# WaveTable.net
KiCad netlist of a schematic drawn in EAGLE
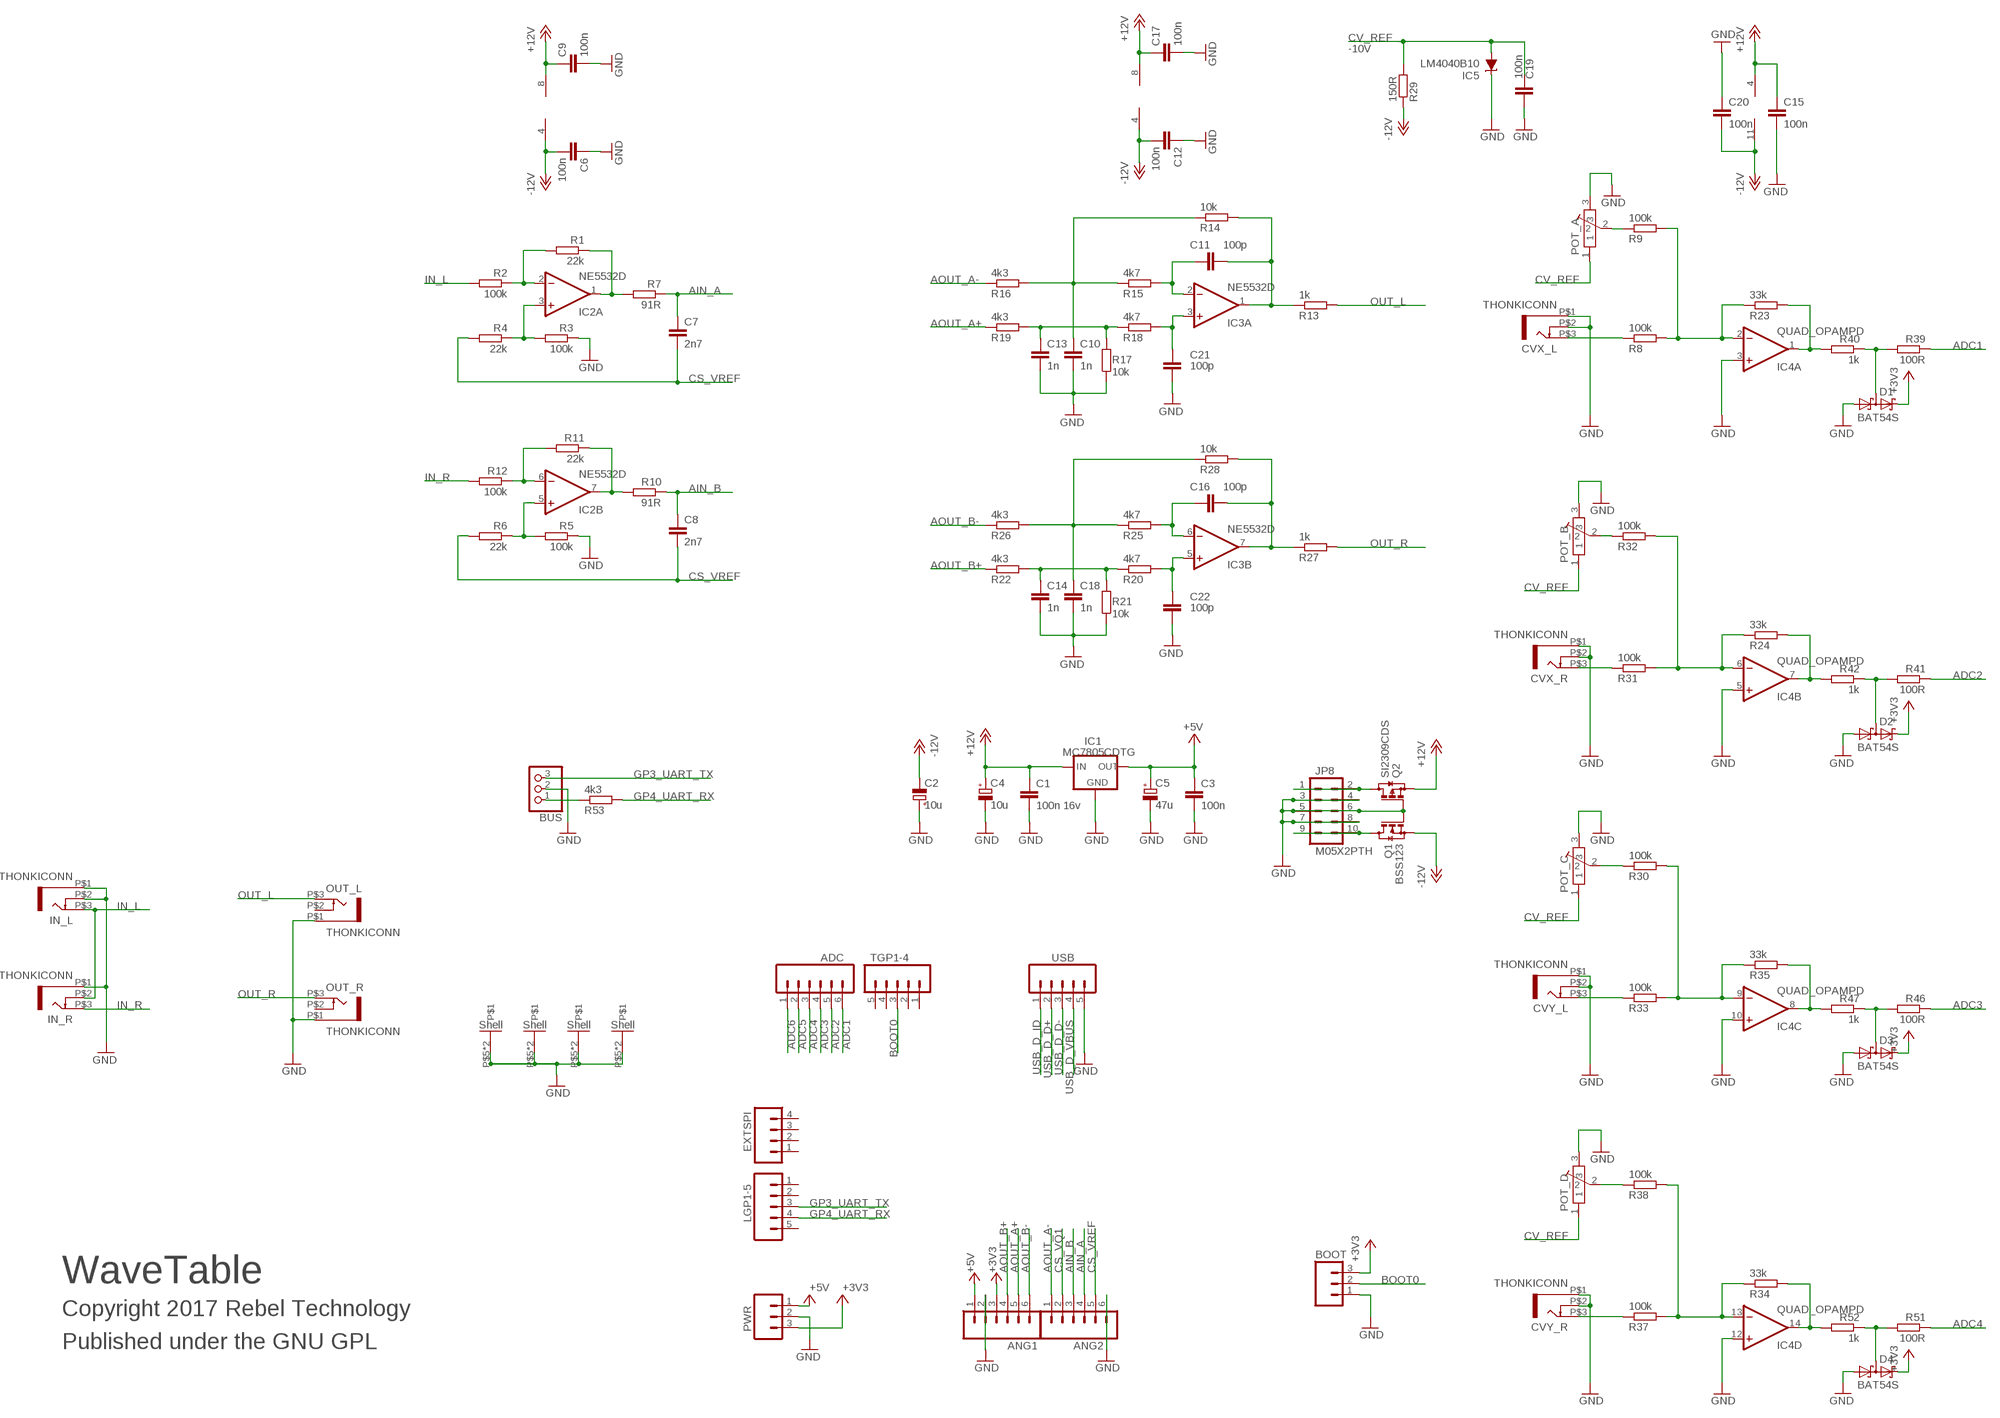
[diagram p0: schematic, sheet 1, part 1 of 2]
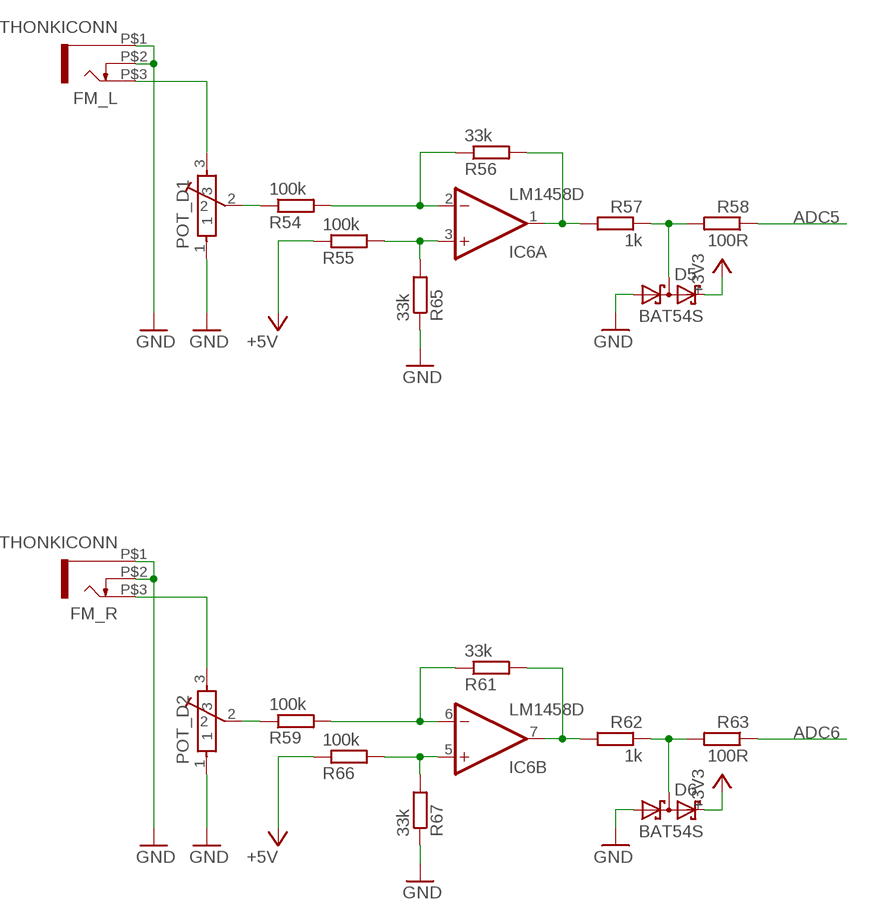
[diagram p1: schematic, sheet 1, part 2 of 2]

(export (version "E")
  (design (tool "Eeschema 10.0.6"))
  (components
    (comp (ref "ADC")
      (value "M06SIP")
      (footprint "eagle-import:1X06")
      (libsource (lib "eagle-import") (part "M06SIP"))
    )
    (comp (ref "ANG1")
      (value "M06SIP")
      (footprint "eagle-import:1X06")
      (libsource (lib "eagle-import") (part "M06SIP"))
    )
    (comp (ref "ANG2")
      (value "M06SIP")
      (footprint "eagle-import:1X06")
      (libsource (lib "eagle-import") (part "M06SIP"))
    )
    (comp (ref "BOOT")
      (value "M03PTH")
      (footprint "eagle-import:1X03")
      (libsource (lib "eagle-import") (part "M03PTH"))
    )
    (comp (ref "BUS")
      (value "CON-JST-1X03PH-TH")
      (footprint "eagle-import:JST-B3B-PH-KL")
      (libsource (lib "eagle-import") (part "CON-JST-1X03PH-TH"))
    )
    (comp (ref "C1")
      (value "100n 16v")
      (footprint "eagle-import:C0603")
      (libsource (lib "eagle-import") (part "C-EUC0603"))
    )
    (comp (ref "C2")
      (value "10u")
      (footprint "eagle-import:CPOL-5")
      (libsource (lib "eagle-import") (part "CPOL-EU153CLV-0505"))
    )
    (comp (ref "C3")
      (value "100n")
      (footprint "eagle-import:C0603")
      (libsource (lib "eagle-import") (part "C-EUC0603"))
    )
    (comp (ref "C4")
      (value "10u")
      (footprint "eagle-import:CPOL-5")
      (libsource (lib "eagle-import") (part "CPOL-EU153CLV-0505"))
    )
    (comp (ref "C5")
      (value "47u")
      (footprint "eagle-import:PANASONIC_C")
      (libsource (lib "eagle-import") (part "rcl_CPOL-EUC"))
    )
    (comp (ref "C6")
      (value "100n")
      (footprint "eagle-import:C0603")
      (libsource (lib "eagle-import") (part "resistor_C-EUC0603"))
    )
    (comp (ref "C7")
      (value "2n7")
      (footprint "eagle-import:C0603")
      (libsource (lib "eagle-import") (part "resistor_C-EUC0603"))
    )
    (comp (ref "C8")
      (value "2n7")
      (footprint "eagle-import:C0603")
      (libsource (lib "eagle-import") (part "resistor_C-EUC0603"))
    )
    (comp (ref "C9")
      (value "100n")
      (footprint "eagle-import:C0603")
      (libsource (lib "eagle-import") (part "resistor_C-EUC0603"))
    )
    (comp (ref "C10")
      (value "1n")
      (footprint "eagle-import:C0603")
      (libsource (lib "eagle-import") (part "resistor_C-EUC0603"))
    )
    (comp (ref "C11")
      (value "100p")
      (footprint "eagle-import:C0603")
      (libsource (lib "eagle-import") (part "resistor_C-EUC0603"))
    )
    (comp (ref "C12")
      (value "100n")
      (footprint "eagle-import:C0603")
      (libsource (lib "eagle-import") (part "resistor_C-EUC0603"))
    )
    (comp (ref "C13")
      (value "1n")
      (footprint "eagle-import:C0603")
      (libsource (lib "eagle-import") (part "resistor_C-EUC0603"))
    )
    (comp (ref "C14")
      (value "1n")
      (footprint "eagle-import:C0603")
      (libsource (lib "eagle-import") (part "resistor_C-EUC0603"))
    )
    (comp (ref "C15")
      (value "100n")
      (footprint "eagle-import:C0603")
      (libsource (lib "eagle-import") (part "resistor_C-EUC0603"))
    )
    (comp (ref "C16")
      (value "100p")
      (footprint "eagle-import:C0603")
      (libsource (lib "eagle-import") (part "resistor_C-EUC0603"))
    )
    (comp (ref "C17")
      (value "100n")
      (footprint "eagle-import:C0603")
      (libsource (lib "eagle-import") (part "resistor_C-EUC0603"))
    )
    (comp (ref "C18")
      (value "1n")
      (footprint "eagle-import:C0603")
      (libsource (lib "eagle-import") (part "resistor_C-EUC0603"))
    )
    (comp (ref "C19")
      (value "100n")
      (footprint "eagle-import:C0603")
      (libsource (lib "eagle-import") (part "resistor_C-EUC0603"))
    )
    (comp (ref "C20")
      (value "100n")
      (footprint "eagle-import:C0603")
      (libsource (lib "eagle-import") (part "resistor_C-EUC0603"))
    )
    (comp (ref "C21")
      (value "100p")
      (footprint "eagle-import:C0603")
      (libsource (lib "eagle-import") (part "resistor_C-EUC0603"))
    )
    (comp (ref "C22")
      (value "100p")
      (footprint "eagle-import:C0603")
      (libsource (lib "eagle-import") (part "resistor_C-EUC0603"))
    )
    (comp (ref "CVX_L")
      (value "THONKICONN")
      (footprint "eagle-import:THONKICONN")
      (libsource (lib "eagle-import") (part "THONKICONN"))
    )
    (comp (ref "CVX_R")
      (value "THONKICONN")
      (footprint "eagle-import:THONKICONN")
      (libsource (lib "eagle-import") (part "THONKICONN"))
    )
    (comp (ref "CVY_L")
      (value "THONKICONN")
      (footprint "eagle-import:THONKICONN")
      (libsource (lib "eagle-import") (part "THONKICONN"))
    )
    (comp (ref "CVY_R")
      (value "THONKICONN")
      (footprint "eagle-import:THONKICONN")
      (libsource (lib "eagle-import") (part "THONKICONN"))
    )
    (comp (ref "D1")
      (value "BAT54S")
      (footprint "eagle-import:SOT23")
      (libsource (lib "eagle-import") (part "BAT54S"))
    )
    (comp (ref "D2")
      (value "BAT54S")
      (footprint "eagle-import:SOT23")
      (libsource (lib "eagle-import") (part "BAT54S"))
    )
    (comp (ref "D3")
      (value "BAT54S")
      (footprint "eagle-import:SOT23")
      (libsource (lib "eagle-import") (part "BAT54S"))
    )
    (comp (ref "D4")
      (value "BAT54S")
      (footprint "eagle-import:SOT23")
      (libsource (lib "eagle-import") (part "BAT54S"))
    )
    (comp (ref "D5")
      (value "BAT54S")
      (footprint "eagle-import:SOT23")
      (libsource (lib "eagle-import") (part "BAT54S"))
    )
    (comp (ref "D6")
      (value "BAT54S")
      (footprint "eagle-import:SOT23")
      (libsource (lib "eagle-import") (part "BAT54S"))
    )
    (comp (ref "EXTSPI")
      (value "M04PTH")
      (footprint "eagle-import:1X04")
      (libsource (lib "eagle-import") (part "M04PTH"))
    )
    (comp (ref "FM_L")
      (value "THONKICONN")
      (footprint "eagle-import:THONKICONN")
      (libsource (lib "eagle-import") (part "THONKICONN"))
    )
    (comp (ref "FM_R")
      (value "THONKICONN")
      (footprint "eagle-import:THONKICONN")
      (libsource (lib "eagle-import") (part "THONKICONN"))
    )
    (comp (ref "IC1")
      (value "MC7805CDTG")
      (footprint "eagle-import:DPACK")
      (libsource (lib "eagle-import") (part "MC78XX"))
    )
    (comp (ref "IC2")
      (value "NE5532D")
      (footprint "eagle-import:SO08")
      (libsource (lib "eagle-import") (part "NE5532D"))
    )
    (comp (ref "IC3")
      (value "NE5532D")
      (footprint "eagle-import:SO08")
      (libsource (lib "eagle-import") (part "NE5532D"))
    )
    (comp (ref "IC4")
      (value "QUAD_OPAMPD")
      (footprint "eagle-import:SO14")
      (libsource (lib "eagle-import") (part "QUAD_OPAMPD"))
    )
    (comp (ref "IC5")
      (value "LM4040B10")
      (footprint "eagle-import:DBZ_R-PDSO-G3")
      (fields (field (name "MF") "TEXAS INSTRUMENT CONNECTORS") (field (name "MPN") "LM4041C12QDBZT"))
      (libsource (lib "eagle-import") (part "LM4041DBZC12"))
    )
    (comp (ref "IC6")
      (value "LM1458D")
      (footprint "eagle-import:SO08")
      (libsource (lib "eagle-import") (part "1458DLM"))
    )
    (comp (ref "IN_L")
      (value "THONKICONN")
      (footprint "eagle-import:THONKICONN")
      (libsource (lib "eagle-import") (part "THONKICONN"))
    )
    (comp (ref "IN_R")
      (value "THONKICONN")
      (footprint "eagle-import:THONKICONN")
      (libsource (lib "eagle-import") (part "THONKICONN"))
    )
    (comp (ref "JP8")
      (value "M05X2PTH")
      (footprint "eagle-import:AVR_ICSP")
      (libsource (lib "eagle-import") (part "M05X2PTH"))
    )
    (comp (ref "LGP1-5")
      (value "M05PTH")
      (footprint "eagle-import:1X05")
      (libsource (lib "eagle-import") (part "M05PTH"))
    )
    (comp (ref "OUT_L")
      (value "THONKICONN")
      (footprint "eagle-import:THONKICONN")
      (libsource (lib "eagle-import") (part "THONKICONN"))
    )
    (comp (ref "OUT_R")
      (value "THONKICONN")
      (footprint "eagle-import:THONKICONN")
      (libsource (lib "eagle-import") (part "THONKICONN"))
    )
    (comp (ref "POT_A")
      (value "POT-ALPS-RK09L1140")
      (footprint "eagle-import:POT-ALPS-RK09L1140")
      (libsource (lib "eagle-import") (part "POT-ALPS-RK09L1140"))
    )
    (comp (ref "POT_B")
      (value "POT-ALPS-RK09L1140")
      (footprint "eagle-import:POT-ALPS-RK09L1140")
      (libsource (lib "eagle-import") (part "POT-ALPS-RK09L1140"))
    )
    (comp (ref "POT_C")
      (value "POT-ALPS-RK09L1140")
      (footprint "eagle-import:POT-ALPS-RK09L1140")
      (libsource (lib "eagle-import") (part "POT-ALPS-RK09L1140"))
    )
    (comp (ref "POT_D")
      (value "POT-ALPS-RK09L1140")
      (footprint "eagle-import:POT-ALPS-RK09L1140")
      (libsource (lib "eagle-import") (part "POT-ALPS-RK09L1140"))
    )
    (comp (ref "POT_D1")
      (value "POT-ALPS-RK09L1140")
      (footprint "eagle-import:POT-ALPS-RK09L1140")
      (libsource (lib "eagle-import") (part "POT-ALPS-RK09L1140"))
    )
    (comp (ref "POT_D2")
      (value "POT-ALPS-RK09L1140")
      (footprint "eagle-import:POT-ALPS-RK09L1140")
      (libsource (lib "eagle-import") (part "POT-ALPS-RK09L1140"))
    )
    (comp (ref "PWR")
      (value "M03PTH")
      (footprint "eagle-import:1X03")
      (libsource (lib "eagle-import") (part "M03PTH"))
    )
    (comp (ref "Q1")
      (value "BSS123")
      (footprint "eagle-import:SOT23")
      (libsource (lib "eagle-import") (part "BSS123"))
    )
    (comp (ref "Q2")
      (value "SI2309CDS")
      (footprint "eagle-import:SOT23")
      (libsource (lib "eagle-import") (part "BSS84"))
    )
    (comp (ref "R1")
      (value "22k")
      (footprint "eagle-import:0603")
      (libsource (lib "eagle-import") (part "R-EU_0603"))
    )
    (comp (ref "R2")
      (value "100k")
      (footprint "eagle-import:0603")
      (libsource (lib "eagle-import") (part "R-EU_0603"))
    )
    (comp (ref "R3")
      (value "100k")
      (footprint "eagle-import:0603")
      (libsource (lib "eagle-import") (part "R-EU_0603"))
    )
    (comp (ref "R4")
      (value "22k")
      (footprint "eagle-import:0603")
      (libsource (lib "eagle-import") (part "R-EU_0603"))
    )
    (comp (ref "R5")
      (value "100k")
      (footprint "eagle-import:0603")
      (libsource (lib "eagle-import") (part "R-EU_0603"))
    )
    (comp (ref "R6")
      (value "22k")
      (footprint "eagle-import:0603")
      (libsource (lib "eagle-import") (part "R-EU_0603"))
    )
    (comp (ref "R7")
      (value "91R")
      (footprint "eagle-import:0603")
      (libsource (lib "eagle-import") (part "R-EU_0603"))
    )
    (comp (ref "R8")
      (value "100k")
      (footprint "eagle-import:0603")
      (libsource (lib "eagle-import") (part "R-EU_0603"))
    )
    (comp (ref "R9")
      (value "100k")
      (footprint "eagle-import:0603")
      (libsource (lib "eagle-import") (part "R-EU_0603"))
    )
    (comp (ref "R10")
      (value "91R")
      (footprint "eagle-import:0603")
      (libsource (lib "eagle-import") (part "R-EU_0603"))
    )
    (comp (ref "R11")
      (value "22k")
      (footprint "eagle-import:0603")
      (libsource (lib "eagle-import") (part "R-EU_0603"))
    )
    (comp (ref "R12")
      (value "100k")
      (footprint "eagle-import:0603")
      (libsource (lib "eagle-import") (part "R-EU_0603"))
    )
    (comp (ref "R13")
      (value "1k")
      (footprint "eagle-import:0603")
      (libsource (lib "eagle-import") (part "R-EU_0603"))
    )
    (comp (ref "R14")
      (value "10k")
      (footprint "eagle-import:0603")
      (libsource (lib "eagle-import") (part "R-EU_0603"))
    )
    (comp (ref "R15")
      (value "4k7")
      (footprint "eagle-import:0603")
      (libsource (lib "eagle-import") (part "R-EU_0603"))
    )
    (comp (ref "R16")
      (value "4k3")
      (footprint "eagle-import:0603")
      (libsource (lib "eagle-import") (part "R-EU_0603"))
    )
    (comp (ref "R17")
      (value "10k")
      (footprint "eagle-import:0603")
      (libsource (lib "eagle-import") (part "R-EU_0603"))
    )
    (comp (ref "R18")
      (value "4k7")
      (footprint "eagle-import:0603")
      (libsource (lib "eagle-import") (part "R-EU_0603"))
    )
    (comp (ref "R19")
      (value "4k3")
      (footprint "eagle-import:0603")
      (libsource (lib "eagle-import") (part "R-EU_0603"))
    )
    (comp (ref "R20")
      (value "4k7")
      (footprint "eagle-import:0603")
      (libsource (lib "eagle-import") (part "R-EU_0603"))
    )
    (comp (ref "R21")
      (value "10k")
      (footprint "eagle-import:0603")
      (libsource (lib "eagle-import") (part "R-EU_0603"))
    )
    (comp (ref "R22")
      (value "4k3")
      (footprint "eagle-import:0603")
      (libsource (lib "eagle-import") (part "R-EU_0603"))
    )
    (comp (ref "R23")
      (value "33k")
      (footprint "eagle-import:0603")
      (libsource (lib "eagle-import") (part "R-EU_0603"))
    )
    (comp (ref "R24")
      (value "33k")
      (footprint "eagle-import:0603")
      (libsource (lib "eagle-import") (part "R-EU_0603"))
    )
    (comp (ref "R25")
      (value "4k7")
      (footprint "eagle-import:0603")
      (libsource (lib "eagle-import") (part "R-EU_0603"))
    )
    (comp (ref "R26")
      (value "4k3")
      (footprint "eagle-import:0603")
      (libsource (lib "eagle-import") (part "R-EU_0603"))
    )
    (comp (ref "R27")
      (value "1k")
      (footprint "eagle-import:0603")
      (libsource (lib "eagle-import") (part "R-EU_0603"))
    )
    (comp (ref "R28")
      (value "10k")
      (footprint "eagle-import:0603")
      (libsource (lib "eagle-import") (part "R-EU_0603"))
    )
    (comp (ref "R29")
      (value "150R")
      (footprint "eagle-import:0603")
      (libsource (lib "eagle-import") (part "R-EU_0603"))
    )
    (comp (ref "R30")
      (value "100k")
      (footprint "eagle-import:0603")
      (libsource (lib "eagle-import") (part "R-EU_0603"))
    )
    (comp (ref "R31")
      (value "100k")
      (footprint "eagle-import:0603")
      (libsource (lib "eagle-import") (part "R-EU_0603"))
    )
    (comp (ref "R32")
      (value "100k")
      (footprint "eagle-import:0603")
      (libsource (lib "eagle-import") (part "R-EU_0603"))
    )
    (comp (ref "R33")
      (value "100k")
      (footprint "eagle-import:0603")
      (libsource (lib "eagle-import") (part "R-EU_0603"))
    )
    (comp (ref "R34")
      (value "33k")
      (footprint "eagle-import:0603")
      (libsource (lib "eagle-import") (part "R-EU_0603"))
    )
    (comp (ref "R35")
      (value "33k")
      (footprint "eagle-import:0603")
      (libsource (lib "eagle-import") (part "R-EU_0603"))
    )
    (comp (ref "R37")
      (value "100k")
      (footprint "eagle-import:0603")
      (libsource (lib "eagle-import") (part "R-EU_0603"))
    )
    (comp (ref "R38")
      (value "100k")
      (footprint "eagle-import:0603")
      (libsource (lib "eagle-import") (part "R-EU_0603"))
    )
    (comp (ref "R39")
      (value "100R")
      (footprint "eagle-import:0603")
      (libsource (lib "eagle-import") (part "R-EU_0603"))
    )
    (comp (ref "R40")
      (value "1k")
      (footprint "eagle-import:0603")
      (libsource (lib "eagle-import") (part "R-EU_0603"))
    )
    (comp (ref "R41")
      (value "100R")
      (footprint "eagle-import:0603")
      (libsource (lib "eagle-import") (part "R-EU_0603"))
    )
    (comp (ref "R42")
      (value "1k")
      (footprint "eagle-import:0603")
      (libsource (lib "eagle-import") (part "R-EU_0603"))
    )
    (comp (ref "R46")
      (value "100R")
      (footprint "eagle-import:0603")
      (libsource (lib "eagle-import") (part "R-EU_0603"))
    )
    (comp (ref "R47")
      (value "1k")
      (footprint "eagle-import:0603")
      (libsource (lib "eagle-import") (part "R-EU_0603"))
    )
    (comp (ref "R51")
      (value "100R")
      (footprint "eagle-import:0603")
      (libsource (lib "eagle-import") (part "R-EU_0603"))
    )
    (comp (ref "R52")
      (value "1k")
      (footprint "eagle-import:0603")
      (libsource (lib "eagle-import") (part "R-EU_0603"))
    )
    (comp (ref "R53")
      (value "4k3")
      (footprint "eagle-import:0603")
      (libsource (lib "eagle-import") (part "R-EU_0603"))
    )
    (comp (ref "R54")
      (value "100k")
      (footprint "eagle-import:0603")
      (libsource (lib "eagle-import") (part "R-EU_0603"))
    )
    (comp (ref "R55")
      (value "100k")
      (footprint "eagle-import:0603")
      (libsource (lib "eagle-import") (part "R-EU_0603"))
    )
    (comp (ref "R56")
      (value "33k")
      (footprint "eagle-import:0603")
      (libsource (lib "eagle-import") (part "R-EU_0603"))
    )
    (comp (ref "R57")
      (value "1k")
      (footprint "eagle-import:0603")
      (libsource (lib "eagle-import") (part "R-EU_0603"))
    )
    (comp (ref "R58")
      (value "100R")
      (footprint "eagle-import:0603")
      (libsource (lib "eagle-import") (part "R-EU_0603"))
    )
    (comp (ref "R59")
      (value "100k")
      (footprint "eagle-import:0603")
      (libsource (lib "eagle-import") (part "R-EU_0603"))
    )
    (comp (ref "R61")
      (value "33k")
      (footprint "eagle-import:0603")
      (libsource (lib "eagle-import") (part "R-EU_0603"))
    )
    (comp (ref "R62")
      (value "1k")
      (footprint "eagle-import:0603")
      (libsource (lib "eagle-import") (part "R-EU_0603"))
    )
    (comp (ref "R63")
      (value "100R")
      (footprint "eagle-import:0603")
      (libsource (lib "eagle-import") (part "R-EU_0603"))
    )
    (comp (ref "R65")
      (value "33k")
      (footprint "eagle-import:0603")
      (libsource (lib "eagle-import") (part "R-EU_0603"))
    )
    (comp (ref "R66")
      (value "100k")
      (footprint "eagle-import:0603")
      (libsource (lib "eagle-import") (part "R-EU_0603"))
    )
    (comp (ref "R67")
      (value "33k")
      (footprint "eagle-import:0603")
      (libsource (lib "eagle-import") (part "R-EU_0603"))
    )
    (comp (ref "TGP1-4")
      (value "M05PTH")
      (footprint "eagle-import:1X05")
      (libsource (lib "eagle-import") (part "M05PTH"))
    )
    (comp (ref "USB")
      (value "M05PTH")
      (footprint "eagle-import:1X05")
      (libsource (lib "eagle-import") (part "M05PTH"))
    )
  )
  (nets
    (net (code "1") (name "+3V3") (class "Default")
      (node (ref "ANG1") (pin "3") (pinfunction "3_3") (pintype "passive"))
      (node (ref "BOOT") (pin "3") (pinfunction "3_3") (pintype "passive"))
      (node (ref "D1") (pin "2") (pinfunction "C2_2") (pintype "passive"))
      (node (ref "D2") (pin "2") (pinfunction "C2_2") (pintype "passive"))
      (node (ref "D3") (pin "2") (pinfunction "C2_2") (pintype "passive"))
      (node (ref "D4") (pin "2") (pinfunction "C2_2") (pintype "passive"))
      (node (ref "D5") (pin "2") (pinfunction "C2_2") (pintype "passive"))
      (node (ref "D6") (pin "2") (pinfunction "C2_2") (pintype "passive"))
      (node (ref "PWR") (pin "3") (pinfunction "3_3") (pintype "passive"))
    )
    (net (code "2") (name "+5V") (class "Default")
      (node (ref "ANG1") (pin "1") (pinfunction "1_1") (pintype "passive"))
      (node (ref "C3") (pin "1") (pinfunction "1_1") (pintype "passive"))
      (node (ref "C5") (pin "+") (pinfunction "+_+") (pintype "passive"))
      (node (ref "IC1") (pin "3") (pinfunction "OUT_3") (pintype "passive"))
      (node (ref "PWR") (pin "1") (pinfunction "1_1") (pintype "passive"))
      (node (ref "R55") (pin "1") (pinfunction "1_1") (pintype "passive"))
      (node (ref "R66") (pin "1") (pinfunction "1_1") (pintype "passive"))
    )
    (net (code "3") (name "+12V") (class "Default")
      (node (ref "C1") (pin "1") (pinfunction "1_1") (pintype "passive"))
      (node (ref "C15") (pin "1") (pinfunction "1_1") (pintype "passive"))
      (node (ref "C17") (pin "1") (pinfunction "1_1") (pintype "passive"))
      (node (ref "C4") (pin "+") (pinfunction "+_+") (pintype "passive"))
      (node (ref "C9") (pin "1") (pinfunction "1_1") (pintype "passive"))
      (node (ref "IC1") (pin "1") (pinfunction "IN_1") (pintype "input"))
      (node (ref "IC2") (pin "8") (pinfunction "V+_8") (pintype "power_in"))
      (node (ref "IC3") (pin "8") (pinfunction "V+_8") (pintype "power_in"))
      (node (ref "IC4") (pin "4") (pinfunction "V+_4") (pintype "power_in"))
      (node (ref "Q2") (pin "2") (pinfunction "S_2") (pintype "passive"))
    )
    (net (code "4") (name "-12V") (class "Default")
      (node (ref "C12") (pin "2") (pinfunction "2_2") (pintype "passive"))
      (node (ref "C2") (pin "-") (pinfunction "-_-") (pintype "passive"))
      (node (ref "C20") (pin "2") (pinfunction "2_2") (pintype "passive"))
      (node (ref "C6") (pin "2") (pinfunction "2_2") (pintype "passive"))
      (node (ref "IC2") (pin "4") (pinfunction "V-_4") (pintype "power_in"))
      (node (ref "IC3") (pin "4") (pinfunction "V-_4") (pintype "power_in"))
      (node (ref "IC4") (pin "11") (pinfunction "V-_11") (pintype "power_in"))
      (node (ref "Q1") (pin "2") (pinfunction "S_2") (pintype "passive"))
      (node (ref "R29") (pin "1") (pinfunction "1_1") (pintype "passive"))
    )
    (net (code "5") (name "/ADC1") (class "Default")
      (node (ref "ADC") (pin "6") (pinfunction "6_6") (pintype "passive"))
      (node (ref "R39") (pin "1") (pinfunction "1_1") (pintype "passive"))
    )
    (net (code "6") (name "/ADC2") (class "Default")
      (node (ref "ADC") (pin "5") (pinfunction "5_5") (pintype "passive"))
      (node (ref "R41") (pin "1") (pinfunction "1_1") (pintype "passive"))
    )
    (net (code "7") (name "/ADC3") (class "Default")
      (node (ref "ADC") (pin "4") (pinfunction "4_4") (pintype "passive"))
      (node (ref "R46") (pin "1") (pinfunction "1_1") (pintype "passive"))
    )
    (net (code "8") (name "/ADC4") (class "Default")
      (node (ref "ADC") (pin "3") (pinfunction "3_3") (pintype "passive"))
      (node (ref "R51") (pin "1") (pinfunction "1_1") (pintype "passive"))
    )
    (net (code "9") (name "/ADC5") (class "Default")
      (node (ref "ADC") (pin "2") (pinfunction "2_2") (pintype "passive"))
      (node (ref "R58") (pin "1") (pinfunction "1_1") (pintype "passive"))
    )
    (net (code "10") (name "/ADC6") (class "Default")
      (node (ref "ADC") (pin "1") (pinfunction "1_1") (pintype "passive"))
      (node (ref "R63") (pin "1") (pinfunction "1_1") (pintype "passive"))
    )
    (net (code "11") (name "/AIN_A") (class "Default")
      (node (ref "ANG2") (pin "4") (pinfunction "4_4") (pintype "passive"))
      (node (ref "C7") (pin "1") (pinfunction "1_1") (pintype "passive"))
      (node (ref "R7") (pin "1") (pinfunction "1_1") (pintype "passive"))
    )
    (net (code "12") (name "/AIN_B") (class "Default")
      (node (ref "ANG2") (pin "3") (pinfunction "3_3") (pintype "passive"))
      (node (ref "C8") (pin "1") (pinfunction "1_1") (pintype "passive"))
      (node (ref "R10") (pin "1") (pinfunction "1_1") (pintype "passive"))
    )
    (net (code "13") (name "/AOUT_A+") (class "Default")
      (node (ref "ANG1") (pin "5") (pinfunction "5_5") (pintype "passive"))
      (node (ref "R19") (pin "1") (pinfunction "1_1") (pintype "passive"))
    )
    (net (code "14") (name "/AOUT_A-") (class "Default")
      (node (ref "ANG2") (pin "1") (pinfunction "1_1") (pintype "passive"))
      (node (ref "R16") (pin "1") (pinfunction "1_1") (pintype "passive"))
    )
    (net (code "15") (name "/AOUT_B+") (class "Default")
      (node (ref "ANG1") (pin "4") (pinfunction "4_4") (pintype "passive"))
      (node (ref "R22") (pin "1") (pinfunction "1_1") (pintype "passive"))
    )
    (net (code "16") (name "/AOUT_B-") (class "Default")
      (node (ref "ANG1") (pin "6") (pinfunction "6_6") (pintype "passive"))
      (node (ref "R26") (pin "1") (pinfunction "1_1") (pintype "passive"))
    )
    (net (code "17") (name "/BOOT0") (class "Default")
      (node (ref "BOOT") (pin "2") (pinfunction "2_2") (pintype "passive"))
      (node (ref "TGP1-4") (pin "3") (pinfunction "3_3") (pintype "passive"))
    )
    (net (code "18") (name "/CS_VQ1") (class "Default")
      (node (ref "ANG2") (pin "2") (pinfunction "2_2") (pintype "passive"))
    )
    (net (code "19") (name "/CS_VREF") (class "Default")
      (node (ref "ANG2") (pin "5") (pinfunction "5_5") (pintype "passive"))
      (node (ref "C7") (pin "2") (pinfunction "2_2") (pintype "passive"))
      (node (ref "C8") (pin "2") (pinfunction "2_2") (pintype "passive"))
      (node (ref "R4") (pin "2") (pinfunction "2_2") (pintype "passive"))
      (node (ref "R6") (pin "2") (pinfunction "2_2") (pintype "passive"))
    )
    (net (code "20") (name "/CV_REF") (class "Default")
      (node (ref "C19") (pin "1") (pinfunction "1_1") (pintype "passive"))
      (node (ref "IC5") (pin "2") (pinfunction "A_2") (pintype "passive"))
      (node (ref "POT_A") (pin "1") (pinfunction "1_1") (pintype "bidirectional"))
      (node (ref "POT_B") (pin "1") (pinfunction "1_1") (pintype "bidirectional"))
      (node (ref "POT_C") (pin "1") (pinfunction "1_1") (pintype "bidirectional"))
      (node (ref "POT_D") (pin "1") (pinfunction "1_1") (pintype "bidirectional"))
      (node (ref "R29") (pin "2") (pinfunction "2_2") (pintype "passive"))
    )
    (net (code "21") (name "/GP3_UART_TX") (class "Default")
      (node (ref "BUS") (pin "3") (pinfunction "3_3") (pintype "passive"))
      (node (ref "LGP1-5") (pin "3") (pinfunction "3_3") (pintype "passive"))
    )
    (net (code "22") (name "/GP4_UART_RX") (class "Default")
      (node (ref "LGP1-5") (pin "4") (pinfunction "4_4") (pintype "passive"))
      (node (ref "R53") (pin "2") (pinfunction "2_2") (pintype "passive"))
    )
    (net (code "23") (name "/IN_L") (class "Default")
      (node (ref "IN_L") (pin "P$3") (pinfunction "3_P$3") (pintype "passive"))
      (node (ref "IN_R") (pin "P$2") (pinfunction "4_P$2") (pintype "passive"))
      (node (ref "R2") (pin "2") (pinfunction "2_2") (pintype "passive"))
    )
    (net (code "24") (name "/IN_R") (class "Default")
      (node (ref "IN_R") (pin "P$3") (pinfunction "3_P$3") (pintype "passive"))
      (node (ref "R12") (pin "2") (pinfunction "2_2") (pintype "passive"))
    )
    (net (code "25") (name "/OUT_L") (class "Default")
      (node (ref "OUT_L") (pin "P$3") (pinfunction "3_P$3") (pintype "passive"))
      (node (ref "R13") (pin "2") (pinfunction "2_2") (pintype "passive"))
    )
    (net (code "26") (name "/OUT_R") (class "Default")
      (node (ref "OUT_R") (pin "P$3") (pinfunction "3_P$3") (pintype "passive"))
      (node (ref "R27") (pin "2") (pinfunction "2_2") (pintype "passive"))
    )
    (net (code "27") (name "/USB_D_D+") (class "Default")
      (node (ref "USB") (pin "2") (pinfunction "2_2") (pintype "passive"))
    )
    (net (code "28") (name "/USB_D_D-") (class "Default")
      (node (ref "USB") (pin "3") (pinfunction "3_3") (pintype "passive"))
    )
    (net (code "29") (name "/USB_D_ID") (class "Default")
      (node (ref "USB") (pin "1") (pinfunction "1_1") (pintype "passive"))
    )
    (net (code "30") (name "/USB_D_VBUS") (class "Default")
      (node (ref "USB") (pin "4") (pinfunction "4_4") (pintype "passive"))
    )
    (net (code "31") (name "GND") (class "Default")
      (node (ref "ANG1") (pin "2") (pinfunction "2_2") (pintype "passive"))
      (node (ref "ANG2") (pin "6") (pinfunction "6_6") (pintype "passive"))
      (node (ref "BOOT") (pin "1") (pinfunction "1_1") (pintype "passive"))
      (node (ref "BUS") (pin "2") (pinfunction "2_2") (pintype "passive"))
      (node (ref "C1") (pin "2") (pinfunction "2_2") (pintype "passive"))
      (node (ref "C10") (pin "2") (pinfunction "2_2") (pintype "passive"))
      (node (ref "C12") (pin "1") (pinfunction "1_1") (pintype "passive"))
      (node (ref "C13") (pin "2") (pinfunction "2_2") (pintype "passive"))
      (node (ref "C14") (pin "2") (pinfunction "2_2") (pintype "passive"))
      (node (ref "C15") (pin "2") (pinfunction "2_2") (pintype "passive"))
      (node (ref "C17") (pin "2") (pinfunction "2_2") (pintype "passive"))
      (node (ref "C18") (pin "2") (pinfunction "2_2") (pintype "passive"))
      (node (ref "C19") (pin "2") (pinfunction "2_2") (pintype "passive"))
      (node (ref "C2") (pin "+") (pinfunction "+_+") (pintype "passive"))
      (node (ref "C20") (pin "1") (pinfunction "1_1") (pintype "passive"))
      (node (ref "C21") (pin "2") (pinfunction "2_2") (pintype "passive"))
      (node (ref "C22") (pin "2") (pinfunction "2_2") (pintype "passive"))
      (node (ref "C3") (pin "2") (pinfunction "2_2") (pintype "passive"))
      (node (ref "C4") (pin "-") (pinfunction "-_-") (pintype "passive"))
      (node (ref "C5") (pin "-") (pinfunction "-_-") (pintype "passive"))
      (node (ref "C6") (pin "1") (pinfunction "1_1") (pintype "passive"))
      (node (ref "C9") (pin "2") (pinfunction "2_2") (pintype "passive"))
      (node (ref "CVX_L") (pin "P$1") (pinfunction "5_P$1") (pintype "passive"))
      (node (ref "CVX_L") (pin "P$2") (pinfunction "4_P$2") (pintype "passive"))
      (node (ref "CVX_R") (pin "P$1") (pinfunction "5_P$1") (pintype "passive"))
      (node (ref "CVX_R") (pin "P$2") (pinfunction "4_P$2") (pintype "passive"))
      (node (ref "CVY_L") (pin "P$1") (pinfunction "5_P$1") (pintype "passive"))
      (node (ref "CVY_L") (pin "P$2") (pinfunction "4_P$2") (pintype "passive"))
      (node (ref "CVY_R") (pin "P$1") (pinfunction "5_P$1") (pintype "passive"))
      (node (ref "CVY_R") (pin "P$2") (pinfunction "4_P$2") (pintype "passive"))
      (node (ref "D1") (pin "1") (pinfunction "A1_1") (pintype "passive"))
      (node (ref "D2") (pin "1") (pinfunction "A1_1") (pintype "passive"))
      (node (ref "D3") (pin "1") (pinfunction "A1_1") (pintype "passive"))
      (node (ref "D4") (pin "1") (pinfunction "A1_1") (pintype "passive"))
      (node (ref "D5") (pin "1") (pinfunction "A1_1") (pintype "passive"))
      (node (ref "D6") (pin "1") (pinfunction "A1_1") (pintype "passive"))
      (node (ref "FM_L") (pin "P$1") (pinfunction "5_P$1") (pintype "passive"))
      (node (ref "FM_L") (pin "P$2") (pinfunction "4_P$2") (pintype "passive"))
      (node (ref "FM_R") (pin "P$1") (pinfunction "5_P$1") (pintype "passive"))
      (node (ref "FM_R") (pin "P$2") (pinfunction "4_P$2") (pintype "passive"))
      (node (ref "IC1") (pin "4") (pinfunction "GND_4") (pintype "input"))
      (node (ref "IC4") (pin "10") (pinfunction "+IN_10") (pintype "input"))
      (node (ref "IC4") (pin "12") (pinfunction "+IN_12") (pintype "input"))
      (node (ref "IC4") (pin "3") (pinfunction "+IN_3") (pintype "input"))
      (node (ref "IC4") (pin "5") (pinfunction "+IN_5") (pintype "input"))
      (node (ref "IC5") (pin "1") (pinfunction "C_1") (pintype "passive"))
      (node (ref "IN_L") (pin "P$1") (pinfunction "5_P$1") (pintype "passive"))
      (node (ref "IN_L") (pin "P$2") (pinfunction "4_P$2") (pintype "passive"))
      (node (ref "IN_R") (pin "P$1") (pinfunction "5_P$1") (pintype "passive"))
      (node (ref "JP8") (pin "3") (pinfunction "3_3") (pintype "passive"))
      (node (ref "JP8") (pin "4") (pinfunction "4_4") (pintype "passive"))
      (node (ref "JP8") (pin "5") (pinfunction "5_5") (pintype "passive"))
      (node (ref "JP8") (pin "6") (pinfunction "6_6") (pintype "passive"))
      (node (ref "JP8") (pin "7") (pinfunction "7_7") (pintype "passive"))
      (node (ref "JP8") (pin "8") (pinfunction "8_8") (pintype "passive"))
      (node (ref "OUT_L") (pin "P$1") (pinfunction "5_P$1") (pintype "passive"))
      (node (ref "OUT_R") (pin "P$1") (pinfunction "5_P$1") (pintype "passive"))
      (node (ref "POT_A") (pin "3") (pinfunction "3_3") (pintype "bidirectional"))
      (node (ref "POT_A") (pin "P$5") (pinfunction "P$1_P$5") (pintype "bidirectional"))
      (node (ref "POT_A") (pin "P$6") (pinfunction "P$1_P$6") (pintype "bidirectional"))
      (node (ref "POT_B") (pin "3") (pinfunction "3_3") (pintype "bidirectional"))
      (node (ref "POT_B") (pin "P$5") (pinfunction "P$1_P$5") (pintype "bidirectional"))
      (node (ref "POT_B") (pin "P$6") (pinfunction "P$1_P$6") (pintype "bidirectional"))
      (node (ref "POT_C") (pin "3") (pinfunction "3_3") (pintype "bidirectional"))
      (node (ref "POT_C") (pin "P$5") (pinfunction "P$1_P$5") (pintype "bidirectional"))
      (node (ref "POT_C") (pin "P$6") (pinfunction "P$1_P$6") (pintype "bidirectional"))
      (node (ref "POT_D") (pin "3") (pinfunction "3_3") (pintype "bidirectional"))
      (node (ref "POT_D") (pin "P$5") (pinfunction "P$1_P$5") (pintype "bidirectional"))
      (node (ref "POT_D") (pin "P$6") (pinfunction "P$1_P$6") (pintype "bidirectional"))
      (node (ref "POT_D1") (pin "1") (pinfunction "1_1") (pintype "bidirectional"))
      (node (ref "POT_D2") (pin "1") (pinfunction "1_1") (pintype "bidirectional"))
      (node (ref "PWR") (pin "2") (pinfunction "2_2") (pintype "passive"))
      (node (ref "Q1") (pin "1") (pinfunction "G_1") (pintype "passive"))
      (node (ref "Q2") (pin "1") (pinfunction "G_1") (pintype "passive"))
      (node (ref "R17") (pin "1") (pinfunction "1_1") (pintype "passive"))
      (node (ref "R21") (pin "1") (pinfunction "1_1") (pintype "passive"))
      (node (ref "R3") (pin "1") (pinfunction "1_1") (pintype "passive"))
      (node (ref "R5") (pin "1") (pinfunction "1_1") (pintype "passive"))
      (node (ref "R65") (pin "1") (pinfunction "1_1") (pintype "passive"))
      (node (ref "R67") (pin "1") (pinfunction "1_1") (pintype "passive"))
      (node (ref "USB") (pin "5") (pinfunction "5_5") (pintype "passive"))
    )
    (net (code "32") (name "Net-(BUS-Pad1)") (class "Default")
      (node (ref "BUS") (pin "1") (pinfunction "1_1") (pintype "passive"))
      (node (ref "R53") (pin "1") (pinfunction "1_1") (pintype "passive"))
    )
    (net (code "33") (name "Net-(C10-Pad1)") (class "Default")
      (node (ref "C10") (pin "1") (pinfunction "1_1") (pintype "passive"))
      (node (ref "R14") (pin "1") (pinfunction "1_1") (pintype "passive"))
      (node (ref "R15") (pin "1") (pinfunction "1_1") (pintype "passive"))
      (node (ref "R16") (pin "2") (pinfunction "2_2") (pintype "passive"))
    )
    (net (code "34") (name "Net-(C13-Pad1)") (class "Default")
      (node (ref "C13") (pin "1") (pinfunction "1_1") (pintype "passive"))
      (node (ref "R17") (pin "2") (pinfunction "2_2") (pintype "passive"))
      (node (ref "R18") (pin "1") (pinfunction "1_1") (pintype "passive"))
      (node (ref "R19") (pin "2") (pinfunction "2_2") (pintype "passive"))
    )
    (net (code "35") (name "Net-(C14-Pad1)") (class "Default")
      (node (ref "C14") (pin "1") (pinfunction "1_1") (pintype "passive"))
      (node (ref "R20") (pin "1") (pinfunction "1_1") (pintype "passive"))
      (node (ref "R21") (pin "2") (pinfunction "2_2") (pintype "passive"))
      (node (ref "R22") (pin "2") (pinfunction "2_2") (pintype "passive"))
    )
    (net (code "36") (name "Net-(C18-Pad1)") (class "Default")
      (node (ref "C18") (pin "1") (pinfunction "1_1") (pintype "passive"))
      (node (ref "R25") (pin "1") (pinfunction "1_1") (pintype "passive"))
      (node (ref "R26") (pin "2") (pinfunction "2_2") (pintype "passive"))
      (node (ref "R28") (pin "1") (pinfunction "1_1") (pintype "passive"))
    )
    (net (code "37") (name "Net-(CVX_L-3)") (class "Default")
      (node (ref "CVX_L") (pin "P$3") (pinfunction "3_P$3") (pintype "passive"))
      (node (ref "R8") (pin "1") (pinfunction "1_1") (pintype "passive"))
    )
    (net (code "38") (name "Net-(CVX_R-3)") (class "Default")
      (node (ref "CVX_R") (pin "P$3") (pinfunction "3_P$3") (pintype "passive"))
      (node (ref "R31") (pin "1") (pinfunction "1_1") (pintype "passive"))
    )
    (net (code "39") (name "Net-(CVY_L-3)") (class "Default")
      (node (ref "CVY_L") (pin "P$3") (pinfunction "3_P$3") (pintype "passive"))
      (node (ref "R33") (pin "1") (pinfunction "1_1") (pintype "passive"))
    )
    (net (code "40") (name "Net-(CVY_R-3)") (class "Default")
      (node (ref "CVY_R") (pin "P$3") (pinfunction "3_P$3") (pintype "passive"))
      (node (ref "R37") (pin "1") (pinfunction "1_1") (pintype "passive"))
    )
    (net (code "41") (name "Net-(D1-C1A2)") (class "Default")
      (node (ref "D1") (pin "3") (pinfunction "C1A2_3") (pintype "passive"))
      (node (ref "R39") (pin "2") (pinfunction "2_2") (pintype "passive"))
      (node (ref "R40") (pin "1") (pinfunction "1_1") (pintype "passive"))
    )
    (net (code "42") (name "Net-(D2-C1A2)") (class "Default")
      (node (ref "D2") (pin "3") (pinfunction "C1A2_3") (pintype "passive"))
      (node (ref "R41") (pin "2") (pinfunction "2_2") (pintype "passive"))
      (node (ref "R42") (pin "1") (pinfunction "1_1") (pintype "passive"))
    )
    (net (code "43") (name "Net-(D3-C1A2)") (class "Default")
      (node (ref "D3") (pin "3") (pinfunction "C1A2_3") (pintype "passive"))
      (node (ref "R46") (pin "2") (pinfunction "2_2") (pintype "passive"))
      (node (ref "R47") (pin "1") (pinfunction "1_1") (pintype "passive"))
    )
    (net (code "44") (name "Net-(D4-C1A2)") (class "Default")
      (node (ref "D4") (pin "3") (pinfunction "C1A2_3") (pintype "passive"))
      (node (ref "R51") (pin "2") (pinfunction "2_2") (pintype "passive"))
      (node (ref "R52") (pin "1") (pinfunction "1_1") (pintype "passive"))
    )
    (net (code "45") (name "Net-(D5-C1A2)") (class "Default")
      (node (ref "D5") (pin "3") (pinfunction "C1A2_3") (pintype "passive"))
      (node (ref "R57") (pin "1") (pinfunction "1_1") (pintype "passive"))
      (node (ref "R58") (pin "2") (pinfunction "2_2") (pintype "passive"))
    )
    (net (code "46") (name "Net-(D6-C1A2)") (class "Default")
      (node (ref "D6") (pin "3") (pinfunction "C1A2_3") (pintype "passive"))
      (node (ref "R62") (pin "1") (pinfunction "1_1") (pintype "passive"))
      (node (ref "R63") (pin "2") (pinfunction "2_2") (pintype "passive"))
    )
    (net (code "47") (name "Net-(FM_L-3)") (class "Default")
      (node (ref "FM_L") (pin "P$3") (pinfunction "3_P$3") (pintype "passive"))
      (node (ref "POT_D1") (pin "3") (pinfunction "3_3") (pintype "bidirectional"))
    )
    (net (code "48") (name "Net-(FM_R-3)") (class "Default")
      (node (ref "FM_R") (pin "P$3") (pinfunction "3_P$3") (pintype "passive"))
      (node (ref "POT_D2") (pin "3") (pinfunction "3_3") (pintype "bidirectional"))
    )
    (net (code "49") (name "Net-(IC2A-+IN)") (class "Default")
      (node (ref "IC2") (pin "3") (pinfunction "+IN_3") (pintype "input"))
      (node (ref "R3") (pin "2") (pinfunction "2_2") (pintype "passive"))
      (node (ref "R4") (pin "1") (pinfunction "1_1") (pintype "passive"))
    )
    (net (code "50") (name "Net-(IC2A--IN)") (class "Default")
      (node (ref "IC2") (pin "2") (pinfunction "-IN_2") (pintype "input"))
      (node (ref "R1") (pin "2") (pinfunction "2_2") (pintype "passive"))
      (node (ref "R2") (pin "1") (pinfunction "1_1") (pintype "passive"))
    )
    (net (code "51") (name "Net-(IC2A-OUT)") (class "Default")
      (node (ref "IC2") (pin "1") (pinfunction "OUT_1") (pintype "output"))
      (node (ref "R1") (pin "1") (pinfunction "1_1") (pintype "passive"))
      (node (ref "R7") (pin "2") (pinfunction "2_2") (pintype "passive"))
    )
    (net (code "52") (name "Net-(IC2B-+IN)") (class "Default")
      (node (ref "IC2") (pin "5") (pinfunction "+IN_5") (pintype "input"))
      (node (ref "R5") (pin "2") (pinfunction "2_2") (pintype "passive"))
      (node (ref "R6") (pin "1") (pinfunction "1_1") (pintype "passive"))
    )
    (net (code "53") (name "Net-(IC2B--IN)") (class "Default")
      (node (ref "IC2") (pin "6") (pinfunction "-IN_6") (pintype "input"))
      (node (ref "R11") (pin "2") (pinfunction "2_2") (pintype "passive"))
      (node (ref "R12") (pin "1") (pinfunction "1_1") (pintype "passive"))
    )
    (net (code "54") (name "Net-(IC2B-OUT)") (class "Default")
      (node (ref "IC2") (pin "7") (pinfunction "OUT_7") (pintype "output"))
      (node (ref "R10") (pin "2") (pinfunction "2_2") (pintype "passive"))
      (node (ref "R11") (pin "1") (pinfunction "1_1") (pintype "passive"))
    )
    (net (code "55") (name "Net-(IC3A-+IN)") (class "Default")
      (node (ref "C21") (pin "1") (pinfunction "1_1") (pintype "passive"))
      (node (ref "IC3") (pin "3") (pinfunction "+IN_3") (pintype "input"))
      (node (ref "R18") (pin "2") (pinfunction "2_2") (pintype "passive"))
    )
    (net (code "56") (name "Net-(IC3A--IN)") (class "Default")
      (node (ref "C11") (pin "1") (pinfunction "1_1") (pintype "passive"))
      (node (ref "IC3") (pin "2") (pinfunction "-IN_2") (pintype "input"))
      (node (ref "R15") (pin "2") (pinfunction "2_2") (pintype "passive"))
    )
    (net (code "57") (name "Net-(IC3A-OUT)") (class "Default")
      (node (ref "C11") (pin "2") (pinfunction "2_2") (pintype "passive"))
      (node (ref "IC3") (pin "1") (pinfunction "OUT_1") (pintype "output"))
      (node (ref "R13") (pin "1") (pinfunction "1_1") (pintype "passive"))
      (node (ref "R14") (pin "2") (pinfunction "2_2") (pintype "passive"))
    )
    (net (code "58") (name "Net-(IC3B-+IN)") (class "Default")
      (node (ref "C22") (pin "1") (pinfunction "1_1") (pintype "passive"))
      (node (ref "IC3") (pin "5") (pinfunction "+IN_5") (pintype "input"))
      (node (ref "R20") (pin "2") (pinfunction "2_2") (pintype "passive"))
    )
    (net (code "59") (name "Net-(IC3B--IN)") (class "Default")
      (node (ref "C16") (pin "1") (pinfunction "1_1") (pintype "passive"))
      (node (ref "IC3") (pin "6") (pinfunction "-IN_6") (pintype "input"))
      (node (ref "R25") (pin "2") (pinfunction "2_2") (pintype "passive"))
    )
    (net (code "60") (name "Net-(IC3B-OUT)") (class "Default")
      (node (ref "C16") (pin "2") (pinfunction "2_2") (pintype "passive"))
      (node (ref "IC3") (pin "7") (pinfunction "OUT_7") (pintype "output"))
      (node (ref "R27") (pin "1") (pinfunction "1_1") (pintype "passive"))
      (node (ref "R28") (pin "2") (pinfunction "2_2") (pintype "passive"))
    )
    (net (code "61") (name "Net-(IC4A--IN)") (class "Default")
      (node (ref "IC4") (pin "2") (pinfunction "-IN_2") (pintype "input"))
      (node (ref "R23") (pin "1") (pinfunction "1_1") (pintype "passive"))
      (node (ref "R8") (pin "2") (pinfunction "2_2") (pintype "passive"))
      (node (ref "R9") (pin "2") (pinfunction "2_2") (pintype "passive"))
    )
    (net (code "62") (name "Net-(IC4A-OUT)") (class "Default")
      (node (ref "IC4") (pin "1") (pinfunction "OUT_1") (pintype "output"))
      (node (ref "R23") (pin "2") (pinfunction "2_2") (pintype "passive"))
      (node (ref "R40") (pin "2") (pinfunction "2_2") (pintype "passive"))
    )
    (net (code "63") (name "Net-(IC4B--IN)") (class "Default")
      (node (ref "IC4") (pin "6") (pinfunction "-IN_6") (pintype "input"))
      (node (ref "R24") (pin "1") (pinfunction "1_1") (pintype "passive"))
      (node (ref "R31") (pin "2") (pinfunction "2_2") (pintype "passive"))
      (node (ref "R32") (pin "2") (pinfunction "2_2") (pintype "passive"))
    )
    (net (code "64") (name "Net-(IC4B-OUT)") (class "Default")
      (node (ref "IC4") (pin "7") (pinfunction "OUT_7") (pintype "output"))
      (node (ref "R24") (pin "2") (pinfunction "2_2") (pintype "passive"))
      (node (ref "R42") (pin "2") (pinfunction "2_2") (pintype "passive"))
    )
    (net (code "65") (name "Net-(IC4C--IN)") (class "Default")
      (node (ref "IC4") (pin "9") (pinfunction "-IN_9") (pintype "input"))
      (node (ref "R30") (pin "2") (pinfunction "2_2") (pintype "passive"))
      (node (ref "R33") (pin "2") (pinfunction "2_2") (pintype "passive"))
      (node (ref "R35") (pin "1") (pinfunction "1_1") (pintype "passive"))
    )
    (net (code "66") (name "Net-(IC4C-OUT)") (class "Default")
      (node (ref "IC4") (pin "8") (pinfunction "OUT_8") (pintype "output"))
      (node (ref "R35") (pin "2") (pinfunction "2_2") (pintype "passive"))
      (node (ref "R47") (pin "2") (pinfunction "2_2") (pintype "passive"))
    )
    (net (code "67") (name "Net-(IC4D--IN)") (class "Default")
      (node (ref "IC4") (pin "13") (pinfunction "-IN_13") (pintype "input"))
      (node (ref "R34") (pin "1") (pinfunction "1_1") (pintype "passive"))
      (node (ref "R37") (pin "2") (pinfunction "2_2") (pintype "passive"))
      (node (ref "R38") (pin "2") (pinfunction "2_2") (pintype "passive"))
    )
    (net (code "68") (name "Net-(IC4D-OUT)") (class "Default")
      (node (ref "IC4") (pin "14") (pinfunction "OUT_14") (pintype "output"))
      (node (ref "R34") (pin "2") (pinfunction "2_2") (pintype "passive"))
      (node (ref "R52") (pin "2") (pinfunction "2_2") (pintype "passive"))
    )
    (net (code "69") (name "Net-(IC6A-+IN)") (class "Default")
      (node (ref "IC6") (pin "3") (pinfunction "+IN_3") (pintype "input"))
      (node (ref "R55") (pin "2") (pinfunction "2_2") (pintype "passive"))
      (node (ref "R65") (pin "2") (pinfunction "2_2") (pintype "passive"))
    )
    (net (code "70") (name "Net-(IC6A--IN)") (class "Default")
      (node (ref "IC6") (pin "2") (pinfunction "-IN_2") (pintype "input"))
      (node (ref "R54") (pin "2") (pinfunction "2_2") (pintype "passive"))
      (node (ref "R56") (pin "1") (pinfunction "1_1") (pintype "passive"))
    )
    (net (code "71") (name "Net-(IC6A-OUT)") (class "Default")
      (node (ref "IC6") (pin "1") (pinfunction "OUT_1") (pintype "output"))
      (node (ref "R56") (pin "2") (pinfunction "2_2") (pintype "passive"))
      (node (ref "R57") (pin "2") (pinfunction "2_2") (pintype "passive"))
    )
    (net (code "72") (name "Net-(IC6B-+IN)") (class "Default")
      (node (ref "IC6") (pin "5") (pinfunction "+IN_5") (pintype "input"))
      (node (ref "R66") (pin "2") (pinfunction "2_2") (pintype "passive"))
      (node (ref "R67") (pin "2") (pinfunction "2_2") (pintype "passive"))
    )
    (net (code "73") (name "Net-(IC6B--IN)") (class "Default")
      (node (ref "IC6") (pin "6") (pinfunction "-IN_6") (pintype "input"))
      (node (ref "R59") (pin "2") (pinfunction "2_2") (pintype "passive"))
      (node (ref "R61") (pin "1") (pinfunction "1_1") (pintype "passive"))
    )
    (net (code "74") (name "Net-(IC6B-OUT)") (class "Default")
      (node (ref "IC6") (pin "7") (pinfunction "OUT_7") (pintype "output"))
      (node (ref "R61") (pin "2") (pinfunction "2_2") (pintype "passive"))
      (node (ref "R62") (pin "2") (pinfunction "2_2") (pintype "passive"))
    )
    (net (code "75") (name "Net-(POT_A-Pad2)") (class "Default")
      (node (ref "POT_A") (pin "2") (pinfunction "2_2") (pintype "bidirectional"))
      (node (ref "R9") (pin "1") (pinfunction "1_1") (pintype "passive"))
    )
    (net (code "76") (name "Net-(POT_B-Pad2)") (class "Default")
      (node (ref "POT_B") (pin "2") (pinfunction "2_2") (pintype "bidirectional"))
      (node (ref "R32") (pin "1") (pinfunction "1_1") (pintype "passive"))
    )
    (net (code "77") (name "Net-(POT_C-Pad2)") (class "Default")
      (node (ref "POT_C") (pin "2") (pinfunction "2_2") (pintype "bidirectional"))
      (node (ref "R30") (pin "1") (pinfunction "1_1") (pintype "passive"))
    )
    (net (code "78") (name "Net-(POT_D-Pad2)") (class "Default")
      (node (ref "POT_D") (pin "2") (pinfunction "2_2") (pintype "bidirectional"))
      (node (ref "R38") (pin "1") (pinfunction "1_1") (pintype "passive"))
    )
    (net (code "79") (name "Net-(POT_D1-Pad2)") (class "Default")
      (node (ref "POT_D1") (pin "2") (pinfunction "2_2") (pintype "bidirectional"))
      (node (ref "R54") (pin "1") (pinfunction "1_1") (pintype "passive"))
    )
    (net (code "80") (name "Net-(POT_D2-Pad2)") (class "Default")
      (node (ref "POT_D2") (pin "2") (pinfunction "2_2") (pintype "bidirectional"))
      (node (ref "R59") (pin "1") (pinfunction "1_1") (pintype "passive"))
    )
    (net (code "81") (name "Net-(Q1-D)") (class "Default")
      (node (ref "JP8") (pin "10") (pinfunction "10_10") (pintype "passive"))
      (node (ref "JP8") (pin "9") (pinfunction "9_9") (pintype "passive"))
      (node (ref "Q1") (pin "3") (pinfunction "D_3") (pintype "passive"))
    )
    (net (code "82") (name "Net-(Q2-D)") (class "Default")
      (node (ref "JP8") (pin "1") (pinfunction "1_1") (pintype "passive"))
      (node (ref "JP8") (pin "2") (pinfunction "2_2") (pintype "passive"))
      (node (ref "Q2") (pin "3") (pinfunction "D_3") (pintype "passive"))
    )
    (net (code "83") (name "unconnected-(EXTSPI-Pad1)") (class "Default")
      (node (ref "EXTSPI") (pin "1") (pinfunction "1_1") (pintype "passive"))
    )
    (net (code "84") (name "unconnected-(EXTSPI-Pad2)") (class "Default")
      (node (ref "EXTSPI") (pin "2") (pinfunction "2_2") (pintype "passive"))
    )
    (net (code "85") (name "unconnected-(EXTSPI-Pad3)") (class "Default")
      (node (ref "EXTSPI") (pin "3") (pinfunction "3_3") (pintype "passive"))
    )
    (net (code "86") (name "unconnected-(EXTSPI-Pad4)") (class "Default")
      (node (ref "EXTSPI") (pin "4") (pinfunction "4_4") (pintype "passive"))
    )
    (net (code "87") (name "unconnected-(LGP1-5-Pad1)") (class "Default")
      (node (ref "LGP1-5") (pin "1") (pinfunction "1_1") (pintype "passive"))
    )
    (net (code "88") (name "unconnected-(LGP1-5-Pad2)") (class "Default")
      (node (ref "LGP1-5") (pin "2") (pinfunction "2_2") (pintype "passive"))
    )
    (net (code "89") (name "unconnected-(LGP1-5-Pad5)") (class "Default")
      (node (ref "LGP1-5") (pin "5") (pinfunction "5_5") (pintype "passive"))
    )
    (net (code "90") (name "unconnected-(OUT_L-4-PadP$2)") (class "Default")
      (node (ref "OUT_L") (pin "P$2") (pinfunction "4_P$2") (pintype "passive"))
    )
    (net (code "91") (name "unconnected-(OUT_R-4-PadP$2)") (class "Default")
      (node (ref "OUT_R") (pin "P$2") (pinfunction "4_P$2") (pintype "passive"))
    )
    (net (code "92") (name "unconnected-(TGP1-4-Pad1)") (class "Default")
      (node (ref "TGP1-4") (pin "1") (pinfunction "1_1") (pintype "passive"))
    )
    (net (code "93") (name "unconnected-(TGP1-4-Pad2)") (class "Default")
      (node (ref "TGP1-4") (pin "2") (pinfunction "2_2") (pintype "passive"))
    )
    (net (code "94") (name "unconnected-(TGP1-4-Pad4)") (class "Default")
      (node (ref "TGP1-4") (pin "4") (pinfunction "4_4") (pintype "passive"))
    )
    (net (code "95") (name "unconnected-(TGP1-4-Pad5)") (class "Default")
      (node (ref "TGP1-4") (pin "5") (pinfunction "5_5") (pintype "passive"))
    )
  )
)
